# knowles_mic.net
KiCad netlist of a schematic drawn in EAGLE
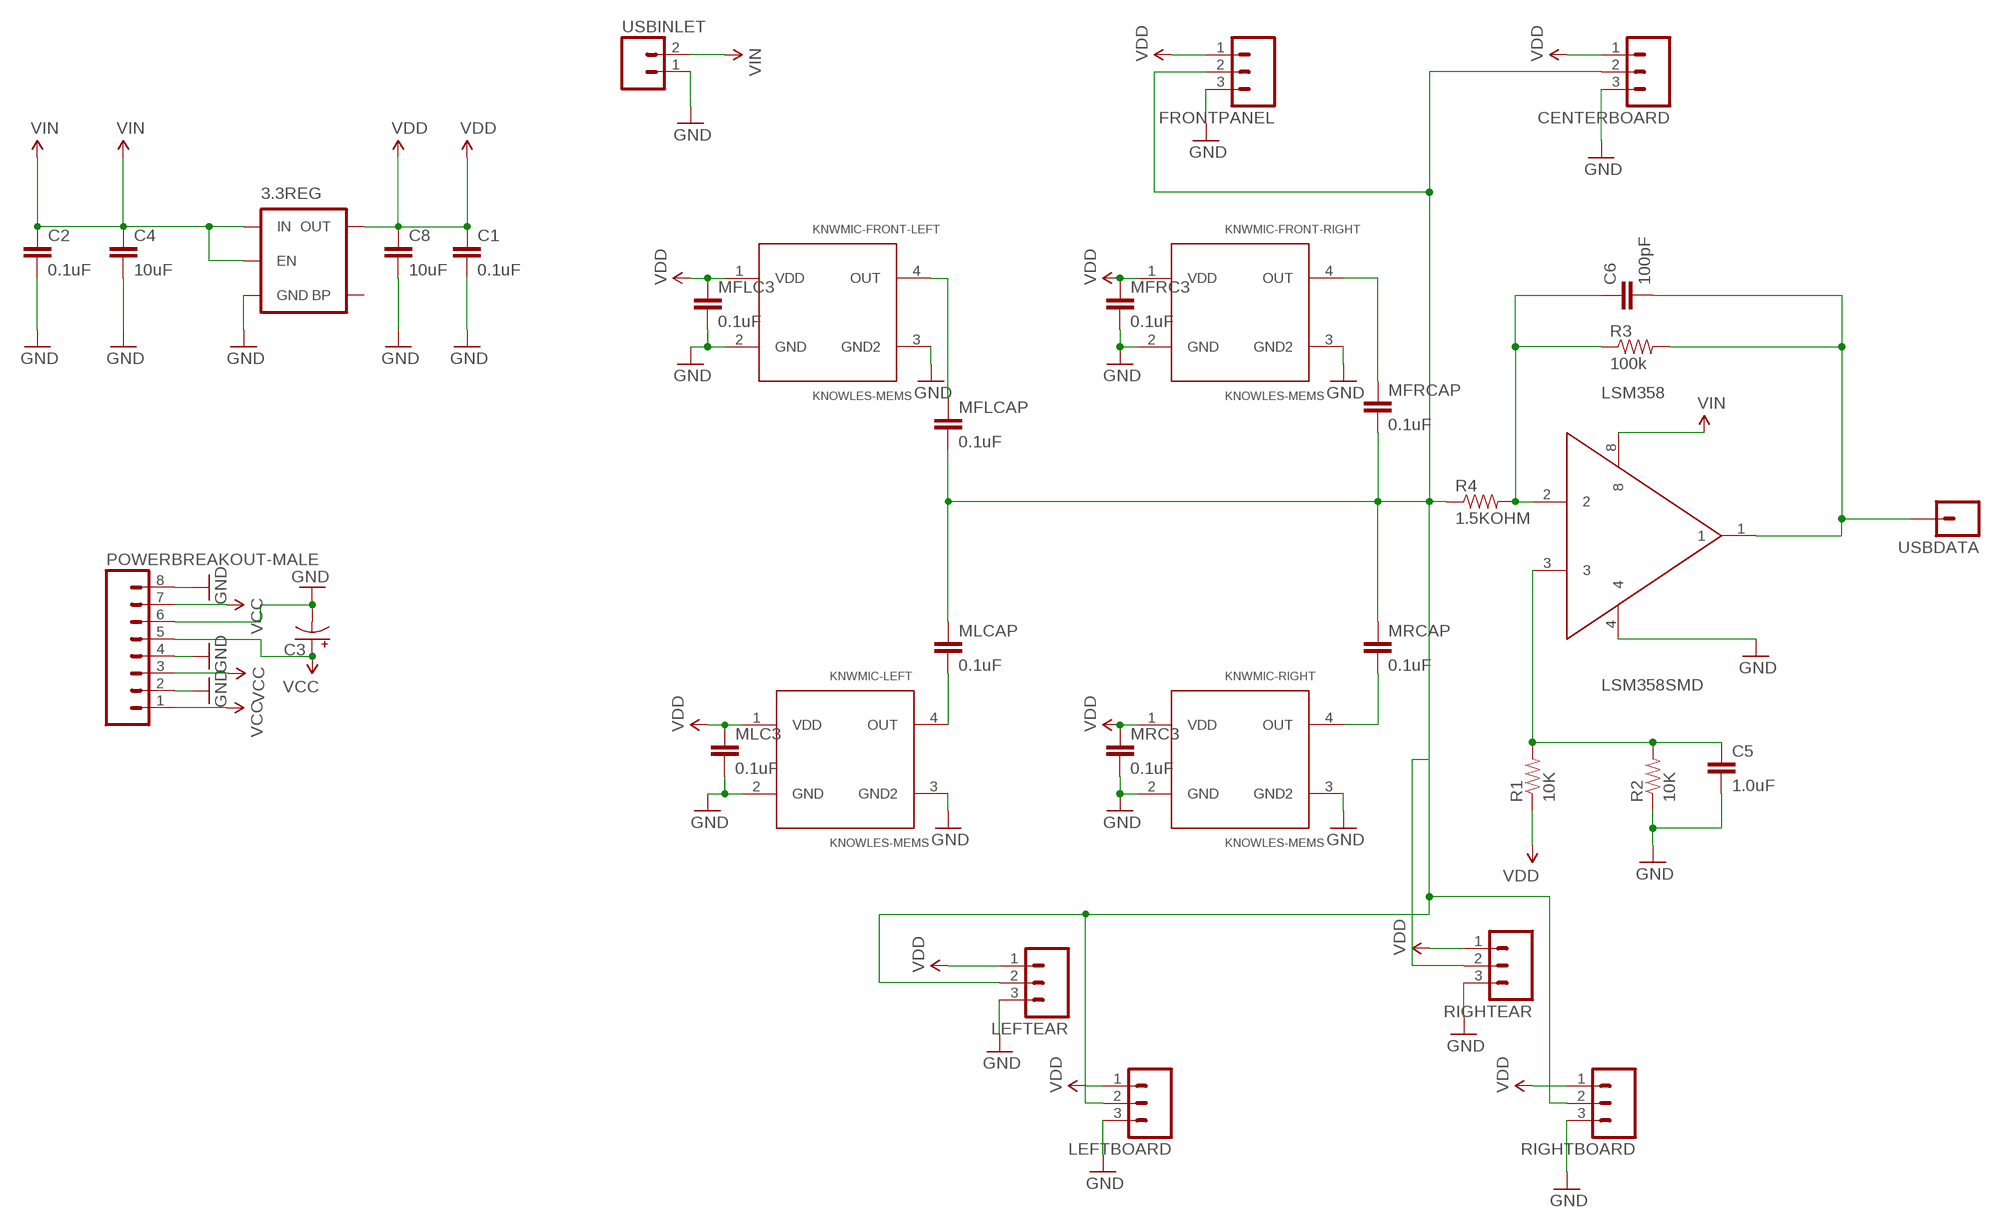
[diagram p0: schematic, sheet 1]

(export (version "E")
  (design (tool "Eeschema 10.0.6"))
  (components
    (comp (ref "3.3REG")
      (value "MIC52053.3V")
      (footprint "eagle-import:SOT23-5")
      (libsource (lib "eagle-import") (part "MIC52053.3V"))
    )
    (comp (ref "C1")
      (value "0.1uF")
      (footprint "eagle-import:0603-CAP")
      (libsource (lib "eagle-import") (part "0.1UF-25V-5%(0603)"))
    )
    (comp (ref "C2")
      (value "0.1uF")
      (footprint "eagle-import:0603-CAP")
      (libsource (lib "eagle-import") (part "0.1UF-25V-5%(0603)"))
    )
    (comp (ref "C3")
      (value "CAP_POLG")
      (footprint "eagle-import:PANASONIC_G")
      (libsource (lib "eagle-import") (part "CAP_POLG"))
    )
    (comp (ref "C4")
      (value "10uF")
      (footprint "eagle-import:0603-CAP")
      (libsource (lib "eagle-import") (part "10UF-6.3V-20%(0603)"))
    )
    (comp (ref "C5")
      (value "1.0uF")
      (footprint "eagle-import:0603-CAP")
      (libsource (lib "eagle-import") (part "1.0UF-16V-10%(0603)"))
    )
    (comp (ref "C6")
      (value "100pF")
      (footprint "eagle-import:0603-CAP")
      (libsource (lib "eagle-import") (part "100PF-50V-5%(0603)"))
    )
    (comp (ref "C8")
      (value "10uF")
      (footprint "eagle-import:0603-CAP")
      (libsource (lib "eagle-import") (part "10UF-6.3V-20%(0603)"))
    )
    (comp (ref "CENTERBOARD")
      (value "M03PTH")
      (footprint "eagle-import:1X03")
      (libsource (lib "eagle-import") (part "M03PTH"))
    )
    (comp (ref "FRONTPANEL")
      (value "M03PTH")
      (footprint "eagle-import:1X03")
      (libsource (lib "eagle-import") (part "M03PTH"))
    )
    (comp (ref "KNWMIC-FRONT-LEFT")
      (value "KNOWLES-MEMS")
      (footprint "eagle-import:MEMS-SPU0410")
      (libsource (lib "eagle-import") (part "KNOWLES-MEMS"))
    )
    (comp (ref "KNWMIC-FRONT-RIGHT")
      (value "KNOWLES-MEMS")
      (footprint "eagle-import:MEMS-SPU0410")
      (libsource (lib "eagle-import") (part "KNOWLES-MEMS"))
    )
    (comp (ref "KNWMIC-LEFT")
      (value "KNOWLES-MEMS")
      (footprint "eagle-import:MEMS-SPU0410")
      (libsource (lib "eagle-import") (part "KNOWLES-MEMS"))
    )
    (comp (ref "KNWMIC-RIGHT")
      (value "KNOWLES-MEMS")
      (footprint "eagle-import:MEMS-SPU0410")
      (libsource (lib "eagle-import") (part "KNOWLES-MEMS"))
    )
    (comp (ref "LEFTBOARD")
      (value "M03PTH")
      (footprint "eagle-import:1X03")
      (libsource (lib "eagle-import") (part "M03PTH"))
    )
    (comp (ref "LEFTEAR")
      (value "M03PTH")
      (footprint "eagle-import:1X03")
      (libsource (lib "eagle-import") (part "M03PTH"))
    )
    (comp (ref "LSM358")
      (value "LSM358SMD")
      (footprint "eagle-import:SOP-8L")
      (libsource (lib "eagle-import") (part "LSM358SMD"))
    )
    (comp (ref "MFLC3")
      (value "0.1uF")
      (footprint "eagle-import:0603-CAP")
      (libsource (lib "eagle-import") (part "0.1UF-25V-5%(0603)"))
    )
    (comp (ref "MFLCAP")
      (value "0.1uF")
      (footprint "eagle-import:0603-CAP")
      (libsource (lib "eagle-import") (part "0.1UF-25V-5%(0603)"))
    )
    (comp (ref "MFRC3")
      (value "0.1uF")
      (footprint "eagle-import:0603-CAP")
      (libsource (lib "eagle-import") (part "0.1UF-25V-5%(0603)"))
    )
    (comp (ref "MFRCAP")
      (value "0.1uF")
      (footprint "eagle-import:0603-CAP")
      (libsource (lib "eagle-import") (part "0.1UF-25V-5%(0603)"))
    )
    (comp (ref "MLC3")
      (value "0.1uF")
      (footprint "eagle-import:0603-CAP")
      (libsource (lib "eagle-import") (part "0.1UF-25V-5%(0603)"))
    )
    (comp (ref "MLCAP")
      (value "0.1uF")
      (footprint "eagle-import:0603-CAP")
      (libsource (lib "eagle-import") (part "0.1UF-25V-5%(0603)"))
    )
    (comp (ref "MRC3")
      (value "0.1uF")
      (footprint "eagle-import:0603-CAP")
      (libsource (lib "eagle-import") (part "0.1UF-25V-5%(0603)"))
    )
    (comp (ref "MRCAP")
      (value "0.1uF")
      (footprint "eagle-import:0603-CAP")
      (libsource (lib "eagle-import") (part "0.1UF-25V-5%(0603)"))
    )
    (comp (ref "POWERBREAKOUT-MALE")
      (value "M08SMD-STRAIGHT-FEMALE")
      (footprint "eagle-import:1X08_SMD")
      (libsource (lib "eagle-import") (part "M08SMD-STRAIGHT-FEMALE"))
    )
    (comp (ref "R1")
      (value "10K")
      (footprint "eagle-import:0603-RES")
      (libsource (lib "eagle-import") (part "10KOHM-1/10W-1%(0603)0603"))
    )
    (comp (ref "R2")
      (value "10K")
      (footprint "eagle-import:0603-RES")
      (libsource (lib "eagle-import") (part "10KOHM-1/10W-1%(0603)0603"))
    )
    (comp (ref "R3")
      (value "100k")
      (footprint "eagle-import:0603-RES")
      (libsource (lib "eagle-import") (part "100KOHM-1/10W-1%(0603)"))
    )
    (comp (ref "R4")
      (value "1.5KOHM")
      (footprint "eagle-import:0603")
      (libsource (lib "eagle-import") (part "1.5KOHM-1/10W-1%(0603)"))
    )
    (comp (ref "RIGHTBOARD")
      (value "M03PTH")
      (footprint "eagle-import:1X03")
      (libsource (lib "eagle-import") (part "M03PTH"))
    )
    (comp (ref "RIGHTEAR")
      (value "M03PTH")
      (footprint "eagle-import:1X03")
      (libsource (lib "eagle-import") (part "M03PTH"))
    )
    (comp (ref "USBDATA")
      (value "M01PTH")
      (footprint "eagle-import:1X01")
      (libsource (lib "eagle-import") (part "M01PTH"))
    )
    (comp (ref "USBINLET")
      (value "M02PTH")
      (footprint "eagle-import:1X02")
      (libsource (lib "eagle-import") (part "M02PTH"))
    )
  )
  (nets
    (net (code "1") (name "GND") (class "Default")
      (node (ref "3.3REG") (pin "2") (pinfunction "GND_2") (pintype "input"))
      (node (ref "C1") (pin "2") (pinfunction "2_2") (pintype "passive"))
      (node (ref "C2") (pin "2") (pinfunction "2_2") (pintype "passive"))
      (node (ref "C3") (pin "-") (pinfunction "-_-") (pintype "passive"))
      (node (ref "C4") (pin "2") (pinfunction "2_2") (pintype "passive"))
      (node (ref "C5") (pin "2") (pinfunction "2_2") (pintype "passive"))
      (node (ref "C8") (pin "2") (pinfunction "2_2") (pintype "passive"))
      (node (ref "CENTERBOARD") (pin "3") (pinfunction "3_3") (pintype "passive"))
      (node (ref "FRONTPANEL") (pin "3") (pinfunction "3_3") (pintype "passive"))
      (node (ref "KNWMIC-FRONT-LEFT") (pin "2") (pinfunction "GND_2") (pintype "bidirectional"))
      (node (ref "KNWMIC-FRONT-LEFT") (pin "3") (pinfunction "GND2_3") (pintype "bidirectional"))
      (node (ref "KNWMIC-FRONT-RIGHT") (pin "2") (pinfunction "GND_2") (pintype "bidirectional"))
      (node (ref "KNWMIC-FRONT-RIGHT") (pin "3") (pinfunction "GND2_3") (pintype "bidirectional"))
      (node (ref "KNWMIC-LEFT") (pin "2") (pinfunction "GND_2") (pintype "bidirectional"))
      (node (ref "KNWMIC-LEFT") (pin "3") (pinfunction "GND2_3") (pintype "bidirectional"))
      (node (ref "KNWMIC-RIGHT") (pin "2") (pinfunction "GND_2") (pintype "bidirectional"))
      (node (ref "KNWMIC-RIGHT") (pin "3") (pinfunction "GND2_3") (pintype "bidirectional"))
      (node (ref "LEFTBOARD") (pin "3") (pinfunction "3_3") (pintype "passive"))
      (node (ref "LEFTEAR") (pin "3") (pinfunction "3_3") (pintype "passive"))
      (node (ref "LSM358") (pin "4") (pinfunction "4_4") (pintype "bidirectional"))
      (node (ref "MFLC3") (pin "2") (pinfunction "2_2") (pintype "passive"))
      (node (ref "MFRC3") (pin "2") (pinfunction "2_2") (pintype "passive"))
      (node (ref "MLC3") (pin "2") (pinfunction "2_2") (pintype "passive"))
      (node (ref "MRC3") (pin "2") (pinfunction "2_2") (pintype "passive"))
      (node (ref "POWERBREAKOUT-MALE") (pin "2") (pinfunction "2_2") (pintype "passive"))
      (node (ref "POWERBREAKOUT-MALE") (pin "4") (pinfunction "4_4") (pintype "passive"))
      (node (ref "POWERBREAKOUT-MALE") (pin "6") (pinfunction "6_6") (pintype "passive"))
      (node (ref "POWERBREAKOUT-MALE") (pin "8") (pinfunction "8_8") (pintype "passive"))
      (node (ref "R2") (pin "1") (pinfunction "1_1") (pintype "passive"))
      (node (ref "RIGHTBOARD") (pin "3") (pinfunction "3_3") (pintype "passive"))
      (node (ref "RIGHTEAR") (pin "3") (pinfunction "3_3") (pintype "passive"))
      (node (ref "USBINLET") (pin "1") (pinfunction "1_1") (pintype "passive"))
    )
    (net (code "2") (name "Net-(C5-Pad1)") (class "Default")
      (node (ref "C5") (pin "1") (pinfunction "1_1") (pintype "passive"))
      (node (ref "LSM358") (pin "3") (pinfunction "3_3") (pintype "bidirectional"))
      (node (ref "R1") (pin "2") (pinfunction "2_2") (pintype "passive"))
      (node (ref "R2") (pin "2") (pinfunction "2_2") (pintype "passive"))
    )
    (net (code "3") (name "Net-(C6-Pad1)") (class "Default")
      (node (ref "C6") (pin "1") (pinfunction "1_1") (pintype "passive"))
      (node (ref "LSM358") (pin "2") (pinfunction "2_2") (pintype "bidirectional"))
      (node (ref "R3") (pin "1") (pinfunction "1_1") (pintype "passive"))
      (node (ref "R4") (pin "2") (pinfunction "2_2") (pintype "passive"))
    )
    (net (code "4") (name "Net-(C6-Pad2)") (class "Default")
      (node (ref "C6") (pin "2") (pinfunction "2_2") (pintype "passive"))
      (node (ref "LSM358") (pin "1") (pinfunction "1_1") (pintype "bidirectional"))
      (node (ref "R3") (pin "2") (pinfunction "2_2") (pintype "passive"))
      (node (ref "USBDATA") (pin "1") (pinfunction "1_1") (pintype "passive"))
    )
    (net (code "5") (name "Net-(CENTERBOARD-Pad2)") (class "Default")
      (node (ref "CENTERBOARD") (pin "2") (pinfunction "2_2") (pintype "passive"))
      (node (ref "FRONTPANEL") (pin "2") (pinfunction "2_2") (pintype "passive"))
      (node (ref "LEFTBOARD") (pin "2") (pinfunction "2_2") (pintype "passive"))
      (node (ref "LEFTEAR") (pin "2") (pinfunction "2_2") (pintype "passive"))
      (node (ref "MFLCAP") (pin "2") (pinfunction "2_2") (pintype "passive"))
      (node (ref "MFRCAP") (pin "2") (pinfunction "2_2") (pintype "passive"))
      (node (ref "MLCAP") (pin "1") (pinfunction "1_1") (pintype "passive"))
      (node (ref "MRCAP") (pin "1") (pinfunction "1_1") (pintype "passive"))
      (node (ref "R4") (pin "1") (pinfunction "1_1") (pintype "passive"))
      (node (ref "RIGHTBOARD") (pin "2") (pinfunction "2_2") (pintype "passive"))
      (node (ref "RIGHTEAR") (pin "2") (pinfunction "2_2") (pintype "passive"))
    )
    (net (code "6") (name "Net-(KNWMIC-FRONT-LEFT-OUT)") (class "Default")
      (node (ref "KNWMIC-FRONT-LEFT") (pin "4") (pinfunction "OUT_4") (pintype "output"))
      (node (ref "MFLCAP") (pin "1") (pinfunction "1_1") (pintype "passive"))
    )
    (net (code "7") (name "Net-(KNWMIC-FRONT-RIGHT-OUT)") (class "Default")
      (node (ref "KNWMIC-FRONT-RIGHT") (pin "4") (pinfunction "OUT_4") (pintype "output"))
      (node (ref "MFRCAP") (pin "1") (pinfunction "1_1") (pintype "passive"))
    )
    (net (code "8") (name "Net-(KNWMIC-LEFT-OUT)") (class "Default")
      (node (ref "KNWMIC-LEFT") (pin "4") (pinfunction "OUT_4") (pintype "output"))
      (node (ref "MLCAP") (pin "2") (pinfunction "2_2") (pintype "passive"))
    )
    (net (code "9") (name "Net-(KNWMIC-RIGHT-OUT)") (class "Default")
      (node (ref "KNWMIC-RIGHT") (pin "4") (pinfunction "OUT_4") (pintype "output"))
      (node (ref "MRCAP") (pin "2") (pinfunction "2_2") (pintype "passive"))
    )
    (net (code "10") (name "VCC") (class "Default")
      (node (ref "C3") (pin "+") (pinfunction "+_+") (pintype "passive"))
      (node (ref "POWERBREAKOUT-MALE") (pin "1") (pinfunction "1_1") (pintype "passive"))
      (node (ref "POWERBREAKOUT-MALE") (pin "3") (pinfunction "3_3") (pintype "passive"))
      (node (ref "POWERBREAKOUT-MALE") (pin "5") (pinfunction "5_5") (pintype "passive"))
      (node (ref "POWERBREAKOUT-MALE") (pin "7") (pinfunction "7_7") (pintype "passive"))
    )
    (net (code "11") (name "VDD") (class "Default")
      (node (ref "3.3REG") (pin "5") (pinfunction "OUT_5") (pintype "passive"))
      (node (ref "C1") (pin "1") (pinfunction "1_1") (pintype "passive"))
      (node (ref "C8") (pin "1") (pinfunction "1_1") (pintype "passive"))
      (node (ref "CENTERBOARD") (pin "1") (pinfunction "1_1") (pintype "passive"))
      (node (ref "FRONTPANEL") (pin "1") (pinfunction "1_1") (pintype "passive"))
      (node (ref "KNWMIC-FRONT-LEFT") (pin "1") (pinfunction "VDD_1") (pintype "power_in"))
      (node (ref "KNWMIC-FRONT-RIGHT") (pin "1") (pinfunction "VDD_1") (pintype "power_in"))
      (node (ref "KNWMIC-LEFT") (pin "1") (pinfunction "VDD_1") (pintype "power_in"))
      (node (ref "KNWMIC-RIGHT") (pin "1") (pinfunction "VDD_1") (pintype "power_in"))
      (node (ref "LEFTBOARD") (pin "1") (pinfunction "1_1") (pintype "passive"))
      (node (ref "LEFTEAR") (pin "1") (pinfunction "1_1") (pintype "passive"))
      (node (ref "MFLC3") (pin "1") (pinfunction "1_1") (pintype "passive"))
      (node (ref "MFRC3") (pin "1") (pinfunction "1_1") (pintype "passive"))
      (node (ref "MLC3") (pin "1") (pinfunction "1_1") (pintype "passive"))
      (node (ref "MRC3") (pin "1") (pinfunction "1_1") (pintype "passive"))
      (node (ref "R1") (pin "1") (pinfunction "1_1") (pintype "passive"))
      (node (ref "RIGHTBOARD") (pin "1") (pinfunction "1_1") (pintype "passive"))
      (node (ref "RIGHTEAR") (pin "1") (pinfunction "1_1") (pintype "passive"))
    )
    (net (code "12") (name "VIN") (class "Default")
      (node (ref "3.3REG") (pin "1") (pinfunction "IN_1") (pintype "input"))
      (node (ref "3.3REG") (pin "3") (pinfunction "EN_3") (pintype "input"))
      (node (ref "C2") (pin "1") (pinfunction "1_1") (pintype "passive"))
      (node (ref "C4") (pin "1") (pinfunction "1_1") (pintype "passive"))
      (node (ref "LSM358") (pin "8") (pinfunction "8_8") (pintype "bidirectional"))
      (node (ref "USBINLET") (pin "2") (pinfunction "2_2") (pintype "passive"))
    )
    (net (code "13") (name "unconnected-(3.3REG-BP-Pad4)") (class "Default")
      (node (ref "3.3REG") (pin "4") (pinfunction "BP_4") (pintype "input"))
    )
  )
)
